# dummyload.net
KiCad netlist of a schematic drawn in EAGLE
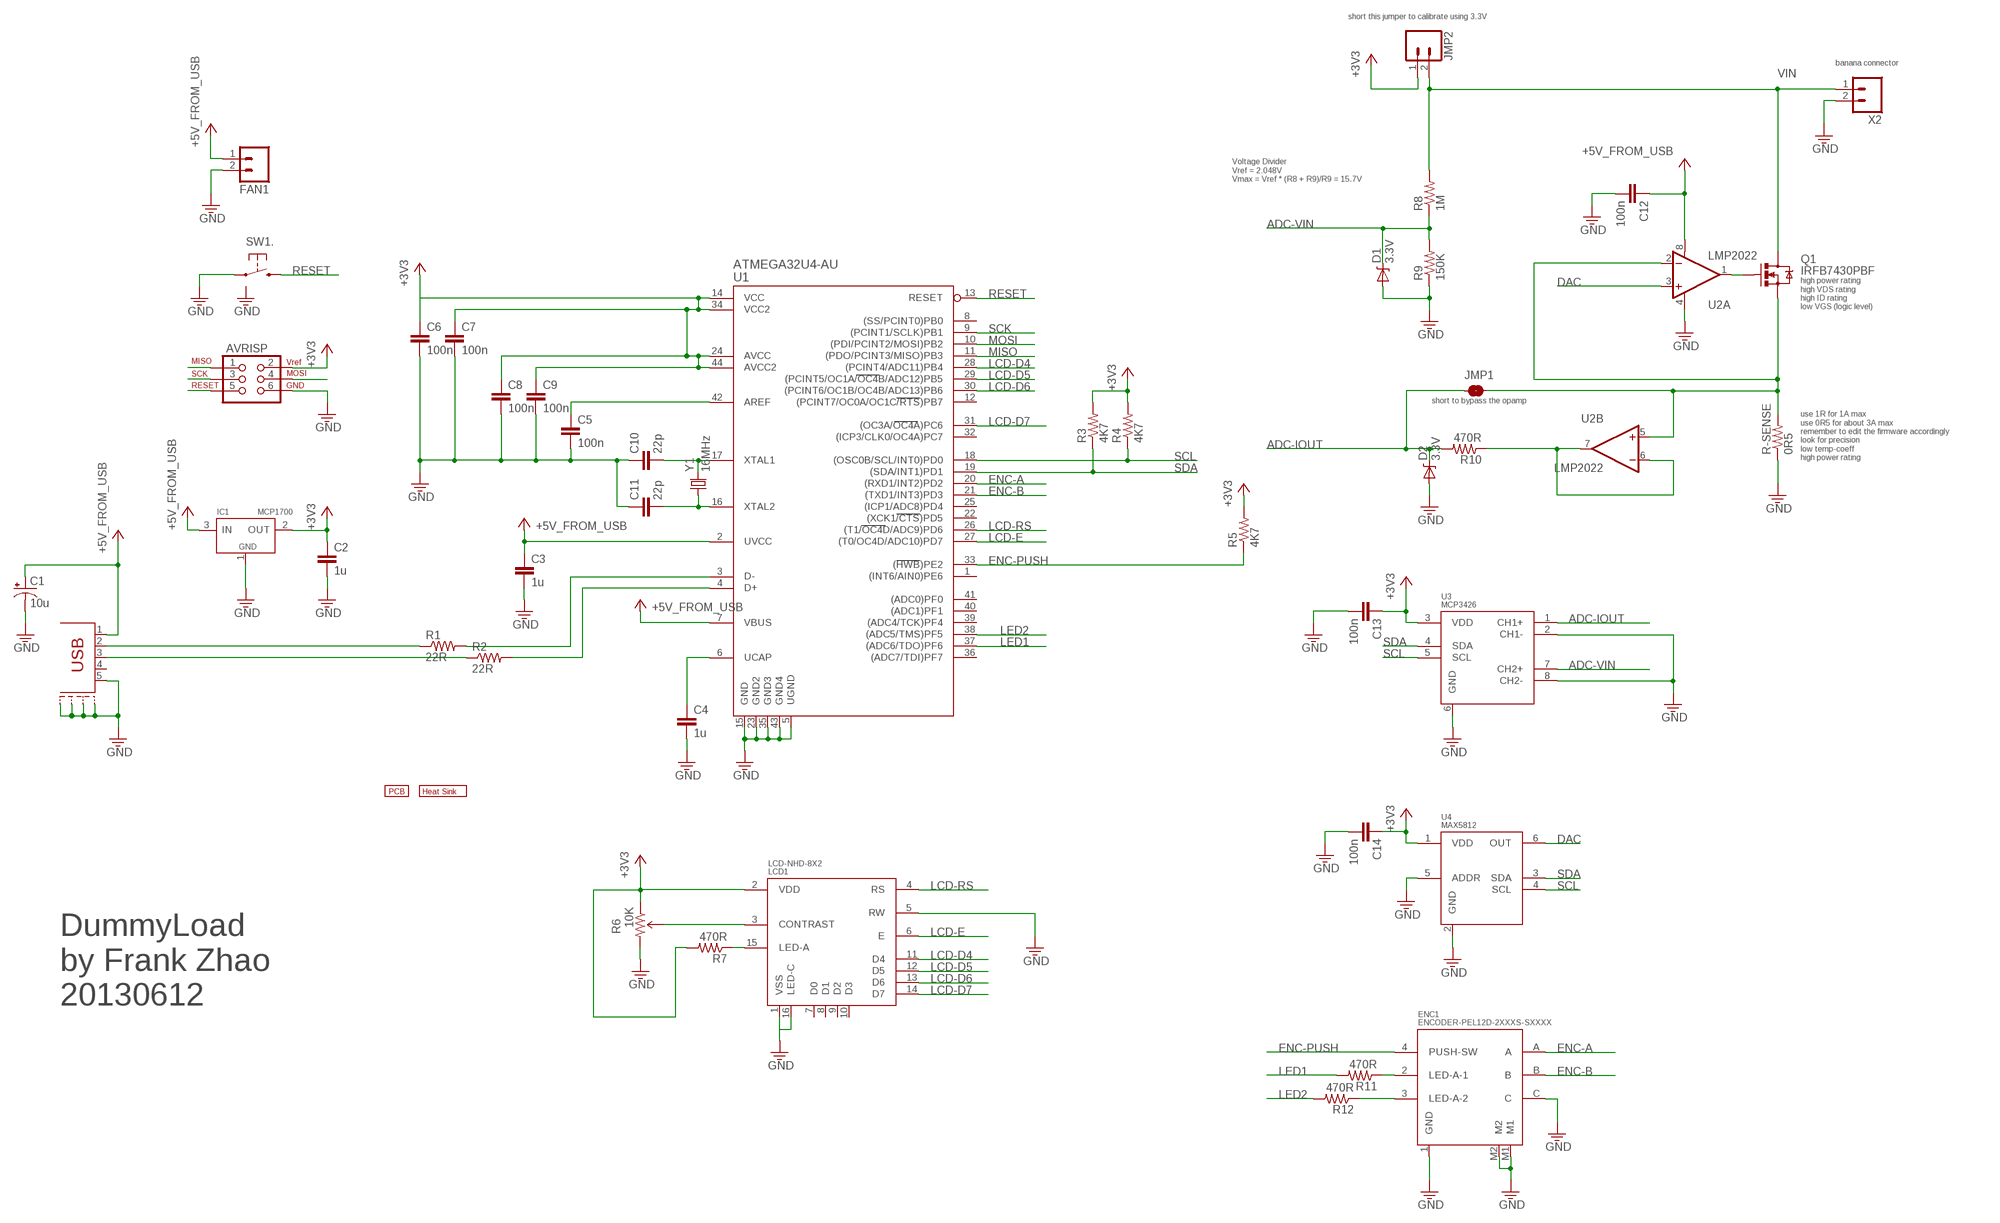
[diagram p0: schematic, sheet 1]

(export (version "E")
  (design (tool "Eeschema 10.0.6"))
  (components
    (comp (ref "AVRISP")
      (value "AVR_SPI_PRG_62X3_LOCK")
      (footprint "eagle-import:2X3_LOCK")
      (libsource (lib "eagle-import") (part "AVR_SPI_PRG_62X3_LOCK"))
    )
    (comp (ref "C1")
      (value "10u")
      (footprint "eagle-import:EIA3216-KIT")
      (libsource (lib "eagle-import") (part "CAP_POL1206-KIT"))
    )
    (comp (ref "C2")
      (value "1u")
      (footprint "eagle-import:0603-CAP")
      (libsource (lib "eagle-import") (part "CAP0603-CAP"))
    )
    (comp (ref "C3")
      (value "1u")
      (footprint "eagle-import:0603-CAP")
      (libsource (lib "eagle-import") (part "CAP0603-CAP"))
    )
    (comp (ref "C4")
      (value "1u")
      (footprint "eagle-import:0603-CAP")
      (libsource (lib "eagle-import") (part "CAP0603-CAP"))
    )
    (comp (ref "C5")
      (value "100n")
      (footprint "eagle-import:0603-CAP")
      (libsource (lib "eagle-import") (part "CAP0603-CAP"))
    )
    (comp (ref "C6")
      (value "100n")
      (footprint "eagle-import:0603-CAP")
      (libsource (lib "eagle-import") (part "CAP0603-CAP"))
    )
    (comp (ref "C7")
      (value "100n")
      (footprint "eagle-import:0603-CAP")
      (libsource (lib "eagle-import") (part "CAP0603-CAP"))
    )
    (comp (ref "C8")
      (value "100n")
      (footprint "eagle-import:0603-CAP")
      (libsource (lib "eagle-import") (part "CAP0603-CAP"))
    )
    (comp (ref "C9")
      (value "100n")
      (footprint "eagle-import:0603-CAP")
      (libsource (lib "eagle-import") (part "CAP0603-CAP"))
    )
    (comp (ref "C10")
      (value "22p")
      (footprint "eagle-import:0603-CAP")
      (libsource (lib "eagle-import") (part "CAP0603-CAP"))
    )
    (comp (ref "C11")
      (value "22p")
      (footprint "eagle-import:0603-CAP")
      (libsource (lib "eagle-import") (part "CAP0603-CAP"))
    )
    (comp (ref "C12")
      (value "100n")
      (footprint "eagle-import:0603-CAP")
      (libsource (lib "eagle-import") (part "CAP0603-CAP"))
    )
    (comp (ref "C13")
      (value "100n")
      (footprint "eagle-import:0603-CAP")
      (libsource (lib "eagle-import") (part "CAP0603-CAP"))
    )
    (comp (ref "C14")
      (value "100n")
      (footprint "eagle-import:0603-CAP")
      (libsource (lib "eagle-import") (part "CAP0603-CAP"))
    )
    (comp (ref "D1")
      (value "3.3V")
      (footprint "eagle-import:SOD-123")
      (libsource (lib "eagle-import") (part "DIODE-ZENER-SOD-123"))
    )
    (comp (ref "D2")
      (value "3.3V")
      (footprint "eagle-import:SOD-123")
      (libsource (lib "eagle-import") (part "DIODE-ZENER-SOD-123"))
    )
    (comp (ref "ENC1")
      (value "ENCODER-PEL12D-2XXXS-SXXXX")
      (footprint "eagle-import:ENCODER-PEL12D-2XXXS-SXXXX")
      (libsource (lib "eagle-import") (part "ENCODER-PEL12D-2XXXS-SXXXX"))
    )
    (comp (ref "FAN1")
      (value "M02PTH")
      (footprint "eagle-import:1X02")
      (libsource (lib "eagle-import") (part "M02PTH"))
    )
    (comp (ref "IC1")
      (value "MCP1700")
      (footprint "eagle-import:SOT23-3")
      (libsource (lib "eagle-import") (part "VREG-MCP1700-SOT23-3"))
    )
    (comp (ref "JMP1")
      (value "SOLDERJUMPERNO")
      (footprint "eagle-import:SJ_2S-NO")
      (libsource (lib "eagle-import") (part "SOLDERJUMPERNO"))
    )
    (comp (ref "JMP2")
      (value "M02-2MM")
      (footprint "eagle-import:1X02_2MM")
      (libsource (lib "eagle-import") (part "M02-2MM"))
    )
    (comp (ref "LCD1")
      (value "LCD-NHD-8X2")
      (footprint "eagle-import:LCD-NHD-8X2-HEADER")
      (libsource (lib "eagle-import") (part "LCD-NHD-8X2"))
    )
    (comp (ref "Q1")
      (value "IRFB7430PBF")
      (footprint "eagle-import:TO220V")
      (libsource (lib "eagle-import") (part "MOSFET-NCHANNELPTH2"))
    )
    (comp (ref "R-SENSE")
      (value "0R5")
      (footprint "eagle-import:D2PACK")
      (libsource (lib "eagle-import") (part "RESISTOR-D2PAK"))
    )
    (comp (ref "R1")
      (value "22R")
      (footprint "eagle-import:0603-RES")
      (libsource (lib "eagle-import") (part "RESISTOR0603-RES"))
    )
    (comp (ref "R2")
      (value "22R")
      (footprint "eagle-import:0603-RES")
      (libsource (lib "eagle-import") (part "RESISTOR0603-RES"))
    )
    (comp (ref "R3")
      (value "4K7")
      (footprint "eagle-import:0603-RES")
      (libsource (lib "eagle-import") (part "RESISTOR0603-RES"))
    )
    (comp (ref "R4")
      (value "4K7")
      (footprint "eagle-import:0603-RES")
      (libsource (lib "eagle-import") (part "RESISTOR0603-RES"))
    )
    (comp (ref "R5")
      (value "4K7")
      (footprint "eagle-import:0603-RES")
      (libsource (lib "eagle-import") (part "RESISTOR0603-RES"))
    )
    (comp (ref "R6")
      (value "10K")
      (footprint "eagle-import:TRIMPOT-3MM")
      (libsource (lib "eagle-import") (part "TRIMPOTSMD"))
    )
    (comp (ref "R7")
      (value "470R")
      (footprint "eagle-import:0603-RES")
      (libsource (lib "eagle-import") (part "RESISTOR0603-RES"))
    )
    (comp (ref "R8")
      (value "1M")
      (footprint "eagle-import:0603-RES")
      (libsource (lib "eagle-import") (part "RESISTOR0603-RES"))
    )
    (comp (ref "R9")
      (value "150K")
      (footprint "eagle-import:0603-RES")
      (libsource (lib "eagle-import") (part "RESISTOR0603-RES"))
    )
    (comp (ref "R10")
      (value "470R")
      (footprint "eagle-import:0603-RES")
      (libsource (lib "eagle-import") (part "RESISTOR0603-RES"))
    )
    (comp (ref "R11")
      (value "470R")
      (footprint "eagle-import:0603-RES")
      (libsource (lib "eagle-import") (part "RESISTOR0603-RES"))
    )
    (comp (ref "R12")
      (value "470R")
      (footprint "eagle-import:0603-RES")
      (libsource (lib "eagle-import") (part "RESISTOR0603-RES"))
    )
    (comp (ref "SW1")
      (value "SWITCH-B3U-1110-BOSS")
      (footprint "eagle-import:SWITCH-TACT-B3U-1100P-B")
      (libsource (lib "eagle-import") (part "SWITCH-B3U-1110-BOSS"))
    )
    (comp (ref "U$1")
      (value "PCB-HAMMOND-RL6115")
      (footprint "eagle-import:PCB-HAMMOND-RL6115")
      (libsource (lib "eagle-import") (part "PCB-HAMMOND-RL6115"))
    )
    (comp (ref "U$2")
      (value "HEATSINK-TO220-VERT-42X25.4")
      (footprint "eagle-import:HEATSINK-TO220-VERT-42X25.4")
      (libsource (lib "eagle-import") (part "HEATSINK-TO220-VERT-42X25.4"))
    )
    (comp (ref "U1")
      (value "ATMEGA32U4-AU")
      (footprint "eagle-import:TQFP44")
      (libsource (lib "eagle-import") (part "ATMEGA32U4-AU"))
    )
    (comp (ref "U2")
      (value "LMP2022")
      (footprint "eagle-import:MSOP-8")
      (libsource (lib "eagle-import") (part "LMP20X2-MSOP8"))
    )
    (comp (ref "U3")
      (value "MCP3426")
      (footprint "eagle-import:MSOP-8")
      (libsource (lib "eagle-import") (part "MCP3426-MSOP8"))
    )
    (comp (ref "U4")
      (value "MAX5812")
      (footprint "eagle-import:SOT23-6")
      (libsource (lib "eagle-import") (part "MAX5812-SOT-23-6"))
    )
    (comp (ref "X1")
      (value "USB-MINI/MICRO-4S-4LEGS")
      (footprint "eagle-import:USB_MICROB_4LEGS")
      (libsource (lib "eagle-import") (part "USB-MINI/MICRO-4S-4LEGS"))
    )
    (comp (ref "X2")
      (value "M025MM")
      (footprint "eagle-import:SCREWTERMINAL-5MM-2")
      (libsource (lib "eagle-import") (part "M025MM"))
    )
    (comp (ref "Y1")
      (value "16MHz")
      (footprint "eagle-import:CRYSTAL-SMD-5X3")
      (libsource (lib "eagle-import") (part "CRYSTAL5X3"))
    )
  )
  (nets
    (net (code "1") (name "+3V3") (class "Default")
      (node (ref "AVRISP") (pin "2") (pinfunction "2_2") (pintype "passive"))
      (node (ref "C13") (pin "1") (pinfunction "1_1") (pintype "passive"))
      (node (ref "C14") (pin "1") (pinfunction "1_1") (pintype "passive"))
      (node (ref "C2") (pin "1") (pinfunction "1_1") (pintype "passive"))
      (node (ref "C6") (pin "1") (pinfunction "1_1") (pintype "passive"))
      (node (ref "C7") (pin "1") (pinfunction "1_1") (pintype "passive"))
      (node (ref "C8") (pin "1") (pinfunction "1_1") (pintype "passive"))
      (node (ref "C9") (pin "1") (pinfunction "1_1") (pintype "passive"))
      (node (ref "IC1") (pin "2") (pinfunction "OUT_2") (pintype "bidirectional"))
      (node (ref "JMP2") (pin "1") (pinfunction "1_1") (pintype "passive"))
      (node (ref "LCD1") (pin "2") (pinfunction "VDD_2") (pintype "bidirectional"))
      (node (ref "R3") (pin "2") (pinfunction "2_2") (pintype "passive"))
      (node (ref "R4") (pin "2") (pinfunction "2_2") (pintype "passive"))
      (node (ref "R5") (pin "2") (pinfunction "2_2") (pintype "passive"))
      (node (ref "R6") (pin "1") (pinfunction "CCW_1") (pintype "passive"))
      (node (ref "R7") (pin "2") (pinfunction "2_2") (pintype "passive"))
      (node (ref "U1") (pin "14") (pinfunction "VCC_14") (pintype "bidirectional"))
      (node (ref "U1") (pin "24") (pinfunction "AVCC_24") (pintype "bidirectional"))
      (node (ref "U1") (pin "34") (pinfunction "VCC2_34") (pintype "bidirectional"))
      (node (ref "U1") (pin "44") (pinfunction "AVCC2_44") (pintype "bidirectional"))
      (node (ref "U3") (pin "3") (pinfunction "VDD_3") (pintype "bidirectional"))
      (node (ref "U4") (pin "1") (pinfunction "VDD_1") (pintype "bidirectional"))
    )
    (net (code "2") (name "+5V_FROM_USB") (class "Default")
      (node (ref "C1") (pin "A") (pinfunction "+_A") (pintype "passive"))
      (node (ref "C12") (pin "1") (pinfunction "1_1") (pintype "passive"))
      (node (ref "C3") (pin "1") (pinfunction "1_1") (pintype "passive"))
      (node (ref "FAN1") (pin "1") (pinfunction "1_1") (pintype "passive"))
      (node (ref "IC1") (pin "3") (pinfunction "IN_3") (pintype "bidirectional"))
      (node (ref "U1") (pin "2") (pinfunction "UVCC_2") (pintype "bidirectional"))
      (node (ref "U1") (pin "7") (pinfunction "VBUS_7") (pintype "bidirectional"))
      (node (ref "U2") (pin "8") (pinfunction "V+_8") (pintype "power_in"))
      (node (ref "X1") (pin "1") (pinfunction "VBUS_1") (pintype "bidirectional"))
    )
    (net (code "3") (name "/ADC-IOUT") (class "Default")
      (node (ref "D2") (pin "C") (pinfunction "C_C") (pintype "passive"))
      (node (ref "JMP1") (pin "1") (pinfunction "1_1") (pintype "passive"))
      (node (ref "R10") (pin "2") (pinfunction "2_2") (pintype "passive"))
      (node (ref "U3") (pin "1") (pinfunction "CH1+_1") (pintype "input"))
    )
    (net (code "4") (name "/ADC-VIN") (class "Default")
      (node (ref "D1") (pin "C") (pinfunction "C_C") (pintype "passive"))
      (node (ref "R8") (pin "1") (pinfunction "1_1") (pintype "passive"))
      (node (ref "R9") (pin "2") (pinfunction "2_2") (pintype "passive"))
      (node (ref "U3") (pin "7") (pinfunction "CH2+_7") (pintype "input"))
    )
    (net (code "5") (name "/DAC") (class "Default")
      (node (ref "U2") (pin "3") (pinfunction "+IN_3") (pintype "input"))
      (node (ref "U4") (pin "6") (pinfunction "OUT_6") (pintype "output"))
    )
    (net (code "6") (name "/ENC-A") (class "Default")
      (node (ref "ENC1") (pin "A") (pinfunction "A_A") (pintype "bidirectional"))
      (node (ref "U1") (pin "20") (pinfunction "(RXD1/INT2)PD2_20") (pintype "bidirectional"))
    )
    (net (code "7") (name "/ENC-B") (class "Default")
      (node (ref "ENC1") (pin "B") (pinfunction "B_B") (pintype "bidirectional"))
      (node (ref "U1") (pin "21") (pinfunction "(TXD1/INT3)PD3_21") (pintype "bidirectional"))
    )
    (net (code "8") (name "/ENC-PUSH") (class "Default")
      (node (ref "ENC1") (pin "4") (pinfunction "PUSH-SW_4") (pintype "bidirectional"))
      (node (ref "R5") (pin "1") (pinfunction "1_1") (pintype "passive"))
      (node (ref "U1") (pin "33") (pinfunction "(HWB)PE2_33") (pintype "bidirectional"))
    )
    (net (code "9") (name "/LCD-D4") (class "Default")
      (node (ref "LCD1") (pin "11") (pinfunction "D4_11") (pintype "bidirectional"))
      (node (ref "U1") (pin "28") (pinfunction "(PCINT4/ADC11)PB4_28") (pintype "bidirectional"))
    )
    (net (code "10") (name "/LCD-D5") (class "Default")
      (node (ref "LCD1") (pin "12") (pinfunction "D5_12") (pintype "bidirectional"))
      (node (ref "U1") (pin "29") (pinfunction "(PCINT5/OC1A/OC4B/ADC12)PB5_29") (pintype "bidirectional"))
    )
    (net (code "11") (name "/LCD-D6") (class "Default")
      (node (ref "LCD1") (pin "13") (pinfunction "D6_13") (pintype "bidirectional"))
      (node (ref "U1") (pin "30") (pinfunction "(PCINT6/OC1B/OC4B/ADC13)PB6_30") (pintype "bidirectional"))
    )
    (net (code "12") (name "/LCD-D7") (class "Default")
      (node (ref "LCD1") (pin "14") (pinfunction "D7_14") (pintype "bidirectional"))
      (node (ref "U1") (pin "31") (pinfunction "(OC3A/OC4A)PC6_31") (pintype "bidirectional"))
    )
    (net (code "13") (name "/LCD-E") (class "Default")
      (node (ref "LCD1") (pin "6") (pinfunction "E_6") (pintype "bidirectional"))
      (node (ref "U1") (pin "27") (pinfunction "(T0/OC4D/ADC10)PD7_27") (pintype "bidirectional"))
    )
    (net (code "14") (name "/LCD-RS") (class "Default")
      (node (ref "LCD1") (pin "4") (pinfunction "RS_4") (pintype "bidirectional"))
      (node (ref "U1") (pin "26") (pinfunction "(T1/OC4D/ADC9)PD6_26") (pintype "bidirectional"))
    )
    (net (code "15") (name "/LED1") (class "Default")
      (node (ref "R11") (pin "2") (pinfunction "2_2") (pintype "passive"))
      (node (ref "U1") (pin "37") (pinfunction "(ADC6/TDO)PF6_37") (pintype "bidirectional"))
    )
    (net (code "16") (name "/LED2") (class "Default")
      (node (ref "R12") (pin "2") (pinfunction "2_2") (pintype "passive"))
      (node (ref "U1") (pin "38") (pinfunction "(ADC5/TMS)PF5_38") (pintype "bidirectional"))
    )
    (net (code "17") (name "/MISO") (class "Default")
      (node (ref "AVRISP") (pin "1") (pinfunction "1_1") (pintype "passive"))
      (node (ref "U1") (pin "11") (pinfunction "(PDO/PCINT3/MISO)PB3_11") (pintype "bidirectional"))
    )
    (net (code "18") (name "/MOSI") (class "Default")
      (node (ref "AVRISP") (pin "4") (pinfunction "4_4") (pintype "passive"))
      (node (ref "U1") (pin "10") (pinfunction "(PDI/PCINT2/MOSI)PB2_10") (pintype "bidirectional"))
    )
    (net (code "19") (name "/RESET") (class "Default")
      (node (ref "AVRISP") (pin "5") (pinfunction "5_5") (pintype "passive"))
      (node (ref "SW1") (pin "2") (pinfunction "2_2") (pintype "passive"))
      (node (ref "U1") (pin "13") (pinfunction "RESET_13") (pintype "bidirectional"))
    )
    (net (code "20") (name "/SCK") (class "Default")
      (node (ref "AVRISP") (pin "3") (pinfunction "3_3") (pintype "passive"))
      (node (ref "U1") (pin "9") (pinfunction "(PCINT1/SCLK)PB1_9") (pintype "bidirectional"))
    )
    (net (code "21") (name "/SCL") (class "Default")
      (node (ref "R4") (pin "1") (pinfunction "1_1") (pintype "passive"))
      (node (ref "U1") (pin "18") (pinfunction "(OSC0B/SCL/INT0)PD0_18") (pintype "bidirectional"))
      (node (ref "U3") (pin "5") (pinfunction "SCL_5") (pintype "bidirectional"))
      (node (ref "U4") (pin "4") (pinfunction "SCL_4") (pintype "bidirectional"))
    )
    (net (code "22") (name "/SDA") (class "Default")
      (node (ref "R3") (pin "1") (pinfunction "1_1") (pintype "passive"))
      (node (ref "U1") (pin "19") (pinfunction "(SDA/INT1)PD1_19") (pintype "bidirectional"))
      (node (ref "U3") (pin "4") (pinfunction "SDA_4") (pintype "bidirectional"))
      (node (ref "U4") (pin "3") (pinfunction "SDA_3") (pintype "bidirectional"))
    )
    (net (code "23") (name "/VIN") (class "Default")
      (node (ref "JMP2") (pin "2") (pinfunction "2_2") (pintype "passive"))
      (node (ref "Q1") (pin "2") (pinfunction "D_2") (pintype "passive"))
      (node (ref "R8") (pin "2") (pinfunction "2_2") (pintype "passive"))
      (node (ref "X2") (pin "1") (pinfunction "1_1") (pintype "passive"))
    )
    (net (code "24") (name "GND") (class "Default")
      (node (ref "AVRISP") (pin "6") (pinfunction "6_6") (pintype "passive"))
      (node (ref "C1") (pin "C") (pinfunction "-_C") (pintype "passive"))
      (node (ref "C10") (pin "1") (pinfunction "1_1") (pintype "passive"))
      (node (ref "C11") (pin "1") (pinfunction "1_1") (pintype "passive"))
      (node (ref "C12") (pin "2") (pinfunction "2_2") (pintype "passive"))
      (node (ref "C13") (pin "2") (pinfunction "2_2") (pintype "passive"))
      (node (ref "C14") (pin "2") (pinfunction "2_2") (pintype "passive"))
      (node (ref "C2") (pin "2") (pinfunction "2_2") (pintype "passive"))
      (node (ref "C3") (pin "2") (pinfunction "2_2") (pintype "passive"))
      (node (ref "C4") (pin "2") (pinfunction "2_2") (pintype "passive"))
      (node (ref "C5") (pin "2") (pinfunction "2_2") (pintype "passive"))
      (node (ref "C6") (pin "2") (pinfunction "2_2") (pintype "passive"))
      (node (ref "C7") (pin "2") (pinfunction "2_2") (pintype "passive"))
      (node (ref "C8") (pin "2") (pinfunction "2_2") (pintype "passive"))
      (node (ref "C9") (pin "2") (pinfunction "2_2") (pintype "passive"))
      (node (ref "D1") (pin "A") (pinfunction "A_A") (pintype "passive"))
      (node (ref "D2") (pin "A") (pinfunction "A_A") (pintype "passive"))
      (node (ref "ENC1") (pin "1") (pinfunction "GND_1") (pintype "bidirectional"))
      (node (ref "ENC1") (pin "C") (pinfunction "C_C") (pintype "bidirectional"))
      (node (ref "ENC1") (pin "M1") (pinfunction "M1_M1") (pintype "bidirectional"))
      (node (ref "ENC1") (pin "M2") (pinfunction "M2_M2") (pintype "bidirectional"))
      (node (ref "FAN1") (pin "2") (pinfunction "2_2") (pintype "passive"))
      (node (ref "IC1") (pin "1") (pinfunction "GND_1") (pintype "bidirectional"))
      (node (ref "LCD1") (pin "1") (pinfunction "VSS_1") (pintype "bidirectional"))
      (node (ref "LCD1") (pin "16") (pinfunction "LED-C_16") (pintype "bidirectional"))
      (node (ref "LCD1") (pin "5") (pinfunction "RW_5") (pintype "bidirectional"))
      (node (ref "R-SENSE") (pin "1") (pinfunction "1_1") (pintype "passive"))
      (node (ref "R6") (pin "3") (pinfunction "CW_3") (pintype "passive"))
      (node (ref "R9") (pin "1") (pinfunction "1_1") (pintype "passive"))
      (node (ref "SW1") (pin "1") (pinfunction "1_1") (pintype "passive"))
      (node (ref "SW1") (pin "BOSS") (pinfunction "P$1_BOSS") (pintype "bidirectional"))
      (node (ref "U1") (pin "15") (pinfunction "GND_15") (pintype "bidirectional"))
      (node (ref "U1") (pin "23") (pinfunction "GND2_23") (pintype "bidirectional"))
      (node (ref "U1") (pin "35") (pinfunction "GND3_35") (pintype "bidirectional"))
      (node (ref "U1") (pin "43") (pinfunction "GND4_43") (pintype "bidirectional"))
      (node (ref "U1") (pin "5") (pinfunction "UGND_5") (pintype "bidirectional"))
      (node (ref "U2") (pin "4") (pinfunction "V-_4") (pintype "power_in"))
      (node (ref "U3") (pin "2") (pinfunction "CH1-_2") (pintype "input"))
      (node (ref "U3") (pin "6") (pinfunction "GND_6") (pintype "bidirectional"))
      (node (ref "U3") (pin "8") (pinfunction "CH2-_8") (pintype "input"))
      (node (ref "U4") (pin "2") (pinfunction "GND_2") (pintype "bidirectional"))
      (node (ref "U4") (pin "5") (pinfunction "ADDR_5") (pintype "input"))
      (node (ref "X1") (pin "5") (pinfunction "GND_5") (pintype "bidirectional"))
      (node (ref "X1") (pin "P$3") (pinfunction "P$1_P$3") (pintype "bidirectional"))
      (node (ref "X1") (pin "P$4") (pinfunction "P$2_P$4") (pintype "bidirectional"))
      (node (ref "X1") (pin "P$7") (pinfunction "P$3_P$7") (pintype "bidirectional"))
      (node (ref "X1") (pin "P$8") (pinfunction "P$4_P$8") (pintype "bidirectional"))
      (node (ref "X2") (pin "2") (pinfunction "2_2") (pintype "passive"))
    )
    (net (code "25") (name "Net-(ENC1-LED-A-1)") (class "Default")
      (node (ref "ENC1") (pin "2") (pinfunction "LED-A-1_2") (pintype "bidirectional"))
      (node (ref "R11") (pin "1") (pinfunction "1_1") (pintype "passive"))
    )
    (net (code "26") (name "Net-(ENC1-LED-A-2)") (class "Default")
      (node (ref "ENC1") (pin "3") (pinfunction "LED-A-2_3") (pintype "bidirectional"))
      (node (ref "R12") (pin "1") (pinfunction "1_1") (pintype "passive"))
    )
    (net (code "27") (name "Net-(LCD1-CONTRAST)") (class "Default")
      (node (ref "LCD1") (pin "3") (pinfunction "CONTRAST_3") (pintype "bidirectional"))
      (node (ref "R6") (pin "2") (pinfunction "WIPER_2") (pintype "passive"))
    )
    (net (code "28") (name "Net-(LCD1-LED-A)") (class "Default")
      (node (ref "LCD1") (pin "15") (pinfunction "LED-A_15") (pintype "bidirectional"))
      (node (ref "R7") (pin "1") (pinfunction "1_1") (pintype "passive"))
    )
    (net (code "29") (name "Net-(Q1-G)") (class "Default")
      (node (ref "Q1") (pin "1") (pinfunction "G_1") (pintype "passive"))
      (node (ref "U2") (pin "1") (pinfunction "OUT_1") (pintype "output"))
    )
    (net (code "30") (name "Net-(Q1-S)") (class "Default")
      (node (ref "JMP1") (pin "2") (pinfunction "2_2") (pintype "passive"))
      (node (ref "Q1") (pin "3") (pinfunction "S_3") (pintype "passive"))
      (node (ref "R-SENSE") (pin "3") (pinfunction "2_3") (pintype "passive"))
      (node (ref "U2") (pin "2") (pinfunction "-IN_2") (pintype "input"))
      (node (ref "U2") (pin "5") (pinfunction "+IN_5") (pintype "input"))
    )
    (net (code "31") (name "Net-(U1-AREF)") (class "Default")
      (node (ref "C5") (pin "1") (pinfunction "1_1") (pintype "passive"))
      (node (ref "U1") (pin "42") (pinfunction "AREF_42") (pintype "bidirectional"))
    )
    (net (code "32") (name "Net-(U1-D+)") (class "Default")
      (node (ref "R2") (pin "2") (pinfunction "2_2") (pintype "passive"))
      (node (ref "U1") (pin "4") (pinfunction "D+_4") (pintype "bidirectional"))
    )
    (net (code "33") (name "Net-(U1-D-)") (class "Default")
      (node (ref "R1") (pin "2") (pinfunction "2_2") (pintype "passive"))
      (node (ref "U1") (pin "3") (pinfunction "D-_3") (pintype "bidirectional"))
    )
    (net (code "34") (name "Net-(U1-UCAP)") (class "Default")
      (node (ref "C4") (pin "1") (pinfunction "1_1") (pintype "passive"))
      (node (ref "U1") (pin "6") (pinfunction "UCAP_6") (pintype "bidirectional"))
    )
    (net (code "35") (name "Net-(U1-XTAL1)") (class "Default")
      (node (ref "C10") (pin "2") (pinfunction "2_2") (pintype "passive"))
      (node (ref "U1") (pin "17") (pinfunction "XTAL1_17") (pintype "bidirectional"))
      (node (ref "Y1") (pin "3") (pinfunction "2_3") (pintype "passive"))
    )
    (net (code "36") (name "Net-(U1-XTAL2)") (class "Default")
      (node (ref "C11") (pin "2") (pinfunction "2_2") (pintype "passive"))
      (node (ref "U1") (pin "16") (pinfunction "XTAL2_16") (pintype "bidirectional"))
      (node (ref "Y1") (pin "1") (pinfunction "1_1") (pintype "passive"))
    )
    (net (code "37") (name "Net-(U2B--IN)") (class "Default")
      (node (ref "R10") (pin "1") (pinfunction "1_1") (pintype "passive"))
      (node (ref "U2") (pin "6") (pinfunction "-IN_6") (pintype "input"))
      (node (ref "U2") (pin "7") (pinfunction "OUT_7") (pintype "output"))
    )
    (net (code "38") (name "Net-(X1-DM)") (class "Default")
      (node (ref "R1") (pin "1") (pinfunction "1_1") (pintype "passive"))
      (node (ref "X1") (pin "2") (pinfunction "DM_2") (pintype "bidirectional"))
    )
    (net (code "39") (name "Net-(X1-DP)") (class "Default")
      (node (ref "R2") (pin "1") (pinfunction "1_1") (pintype "passive"))
      (node (ref "X1") (pin "3") (pinfunction "DP_3") (pintype "bidirectional"))
    )
    (net (code "40") (name "unconnected-(LCD1-D0-Pad7)") (class "Default")
      (node (ref "LCD1") (pin "7") (pinfunction "D0_7") (pintype "bidirectional"))
    )
    (net (code "41") (name "unconnected-(LCD1-D1-Pad8)") (class "Default")
      (node (ref "LCD1") (pin "8") (pinfunction "D1_8") (pintype "bidirectional"))
    )
    (net (code "42") (name "unconnected-(LCD1-D2-Pad9)") (class "Default")
      (node (ref "LCD1") (pin "9") (pinfunction "D2_9") (pintype "bidirectional"))
    )
    (net (code "43") (name "unconnected-(LCD1-D3-Pad10)") (class "Default")
      (node (ref "LCD1") (pin "10") (pinfunction "D3_10") (pintype "bidirectional"))
    )
    (net (code "44") (name "unconnected-(U1-(ADC0)PF0-Pad41)") (class "Default")
      (node (ref "U1") (pin "41") (pinfunction "(ADC0)PF0_41") (pintype "bidirectional"))
    )
    (net (code "45") (name "unconnected-(U1-(ADC1)PF1-Pad40)") (class "Default")
      (node (ref "U1") (pin "40") (pinfunction "(ADC1)PF1_40") (pintype "bidirectional"))
    )
    (net (code "46") (name "unconnected-(U1-(ADC4{slash}TCK)PF4-Pad39)") (class "Default")
      (node (ref "U1") (pin "39") (pinfunction "(ADC4/TCK)PF4_39") (pintype "bidirectional"))
    )
    (net (code "47") (name "unconnected-(U1-(ADC7{slash}TDI)PF7-Pad36)") (class "Default")
      (node (ref "U1") (pin "36") (pinfunction "(ADC7/TDI)PF7_36") (pintype "bidirectional"))
    )
    (net (code "48") (name "unconnected-(U1-(ICP1{slash}ADC8)PD4-Pad25)") (class "Default")
      (node (ref "U1") (pin "25") (pinfunction "(ICP1/ADC8)PD4_25") (pintype "bidirectional"))
    )
    (net (code "49") (name "unconnected-(U1-(ICP3{slash}CLK0{slash}OC4A)PC7-Pad32)") (class "Default")
      (node (ref "U1") (pin "32") (pinfunction "(ICP3/CLK0/OC4A)PC7_32") (pintype "bidirectional"))
    )
    (net (code "50") (name "unconnected-(U1-(INT6{slash}AIN0)PE6-Pad1)") (class "Default")
      (node (ref "U1") (pin "1") (pinfunction "(INT6/AIN0)PE6_1") (pintype "bidirectional"))
    )
    (net (code "51") (name "unconnected-(U1-(PCINT7{slash}OC0A{slash}OC1C{slash}RTS)PB7-Pad12)") (class "Default")
      (node (ref "U1") (pin "12") (pinfunction "(PCINT7/OC0A/OC1C/RTS)PB7_12") (pintype "bidirectional"))
    )
    (net (code "52") (name "unconnected-(U1-(SS{slash}PCINT0)PB0-Pad8)") (class "Default")
      (node (ref "U1") (pin "8") (pinfunction "(SS/PCINT0)PB0_8") (pintype "bidirectional"))
    )
    (net (code "53") (name "unconnected-(U1-(XCK1{slash}CTS)PD5-Pad22)") (class "Default")
      (node (ref "U1") (pin "22") (pinfunction "(XCK1/CTS)PD5_22") (pintype "bidirectional"))
    )
    (net (code "54") (name "unconnected-(X1-ID-Pad4)") (class "Default")
      (node (ref "X1") (pin "4") (pinfunction "ID_4") (pintype "bidirectional"))
    )
  )
)
